# radio.net
KiCad netlist of a schematic drawn in Altium Designer
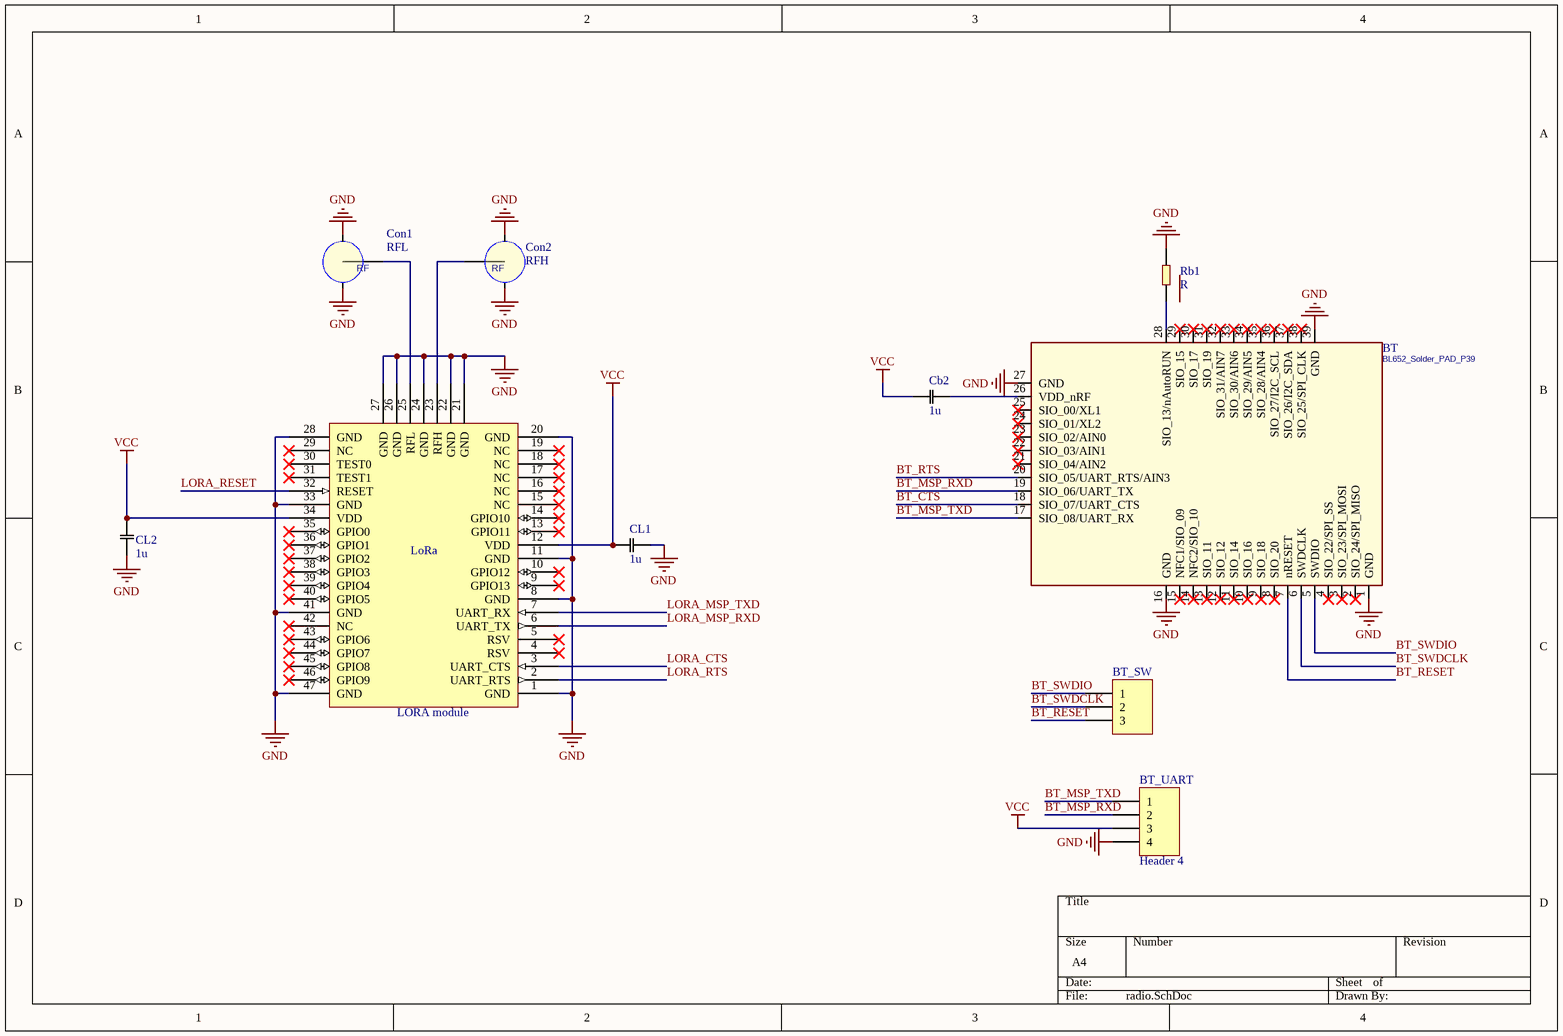
[diagram p0: radio.SchDoc]

(export (version "E")
  (design (tool "Eeschema 10.0.6"))
  (components
    (comp (ref "BT")
      (value "BL652_Solder_PAD_P39")
      (footprint "XCVR_BL652-SA-01")
      (description "BL652 Solder PAD")
      (libsource (lib "env_sens") (part "BL652_Solder_PAD_P39"))
    )
    (comp (ref "BT_SW")
      (value "~")
      (footprint "HDR1X3")
      (description "Header, 3-Pin")
      (fields (field (name "PUBLISHER") "Altium Limited"))
      (libsource (lib "Miscellaneous Connectors") (part "Header 3"))
    )
    (comp (ref "BT_UART")
      (value "Header 4")
      (footprint "HDR1X4")
      (description "Header, 4-Pin")
      (fields (field (name "PUBLISHER") "Altium Limited"))
      (libsource (lib "Miscellaneous Connectors") (part "Header 4"))
    )
    (comp (ref "Cb2")
      (value "1u")
      (footprint "603")
      (description "Capacitor")
      (libsource (lib "pass_comp") (part "C"))
    )
    (comp (ref "CL1")
      (value "1u")
      (footprint "603")
      (description "Capacitor")
      (libsource (lib "pass_comp") (part "C"))
    )
    (comp (ref "CL2")
      (value "1u")
      (footprint "603")
      (description "Capacitor")
      (libsource (lib "pass_comp") (part "C"))
    )
    (comp (ref "Con1")
      (value "RFL")
      (footprint "IPEX")
      (description "SMA PCB Edge Receptacle")
      (libsource (lib "env_sens") (part "IPEX/U.FL"))
    )
    (comp (ref "Con2")
      (value "RFH")
      (footprint "IPEX")
      (description "SMA PCB Edge Receptacle")
      (libsource (lib "env_sens") (part "IPEX/U.FL"))
    )
    (comp (ref "LoRa") (value "LORA module") (footprint "RN2483") (libsource (lib "env_sens") (part "Lora")))
    (comp (ref "Rb1")
      (value "R")
      (footprint "603")
      (description "Resistor")
      (libsource (lib "pass_comp") (part "R"))
    )
  )
  (nets
    (net (code "1") (name "/BT_CTS") (class "Default")
      (node (ref "BT") (pin "18") (pinfunction "SIO_07/UART_CTS_18") (pintype "passive"))
    )
    (net (code "2") (name "/BT_MSP_RXD") (class "Default")
      (node (ref "BT") (pin "19") (pinfunction "SIO_06/UART_TX_19") (pintype "passive"))
      (node (ref "BT_UART") (pin "2") (pinfunction "2_2") (pintype "passive"))
    )
    (net (code "3") (name "/BT_MSP_TXD") (class "Default")
      (node (ref "BT") (pin "17") (pinfunction "SIO_08/UART_RX_17") (pintype "passive"))
      (node (ref "BT_UART") (pin "1") (pinfunction "1_1") (pintype "passive"))
    )
    (net (code "4") (name "/BT_RESET") (class "Default")
      (node (ref "BT") (pin "7") (pinfunction "nRESET_7") (pintype "passive"))
      (node (ref "BT_SW") (pin "3") (pinfunction "3_3") (pintype "passive"))
    )
    (net (code "5") (name "/BT_RTS") (class "Default")
      (node (ref "BT") (pin "20") (pinfunction "SIO_05/UART_RTS/AIN3_20") (pintype "passive"))
    )
    (net (code "6") (name "/BT_SWDCLK") (class "Default")
      (node (ref "BT") (pin "6") (pinfunction "SWDCLK_6") (pintype "passive"))
      (node (ref "BT_SW") (pin "2") (pinfunction "2_2") (pintype "passive"))
    )
    (net (code "7") (name "/BT_SWDIO") (class "Default")
      (node (ref "BT") (pin "5") (pinfunction "SWDIO_5") (pintype "passive"))
      (node (ref "BT_SW") (pin "1") (pinfunction "1_1") (pintype "passive"))
    )
    (net (code "8") (name "/LORA_CTS") (class "Default")
      (node (ref "LoRa") (pin "3") (pinfunction "UART_CTS_3") (pintype "input"))
    )
    (net (code "9") (name "/LORA_MSP_RXD") (class "Default")
      (node (ref "LoRa") (pin "6") (pinfunction "UART_TX_6") (pintype "output"))
    )
    (net (code "10") (name "/LORA_MSP_TXD") (class "Default")
      (node (ref "LoRa") (pin "7") (pinfunction "UART_RX_7") (pintype "input"))
    )
    (net (code "11") (name "/LORA_RESET") (class "Default")
      (node (ref "LoRa") (pin "32") (pinfunction "RESET_32") (pintype "input"))
    )
    (net (code "12") (name "/LORA_RTS") (class "Default")
      (node (ref "LoRa") (pin "2") (pinfunction "UART_RTS_2") (pintype "output"))
    )
    (net (code "13") (name "GND") (class "Default")
      (node (ref "BT") (pin "1") (pinfunction "GND_1") (pintype "passive"))
      (node (ref "BT") (pin "16") (pinfunction "GND_16") (pintype "passive"))
      (node (ref "BT") (pin "27") (pinfunction "GND_27") (pintype "passive"))
      (node (ref "BT") (pin "39") (pinfunction "GND_39") (pintype "passive"))
      (node (ref "BT_UART") (pin "4") (pinfunction "4_4") (pintype "passive"))
      (node (ref "CL1") (pin "2") (pintype "passive"))
      (node (ref "CL2") (pin "1") (pintype "passive"))
      (node (ref "Con1") (pin "2") (pintype "passive"))
      (node (ref "Con1") (pin "3") (pintype "passive"))
      (node (ref "Con2") (pin "2") (pintype "passive"))
      (node (ref "Con2") (pin "3") (pintype "passive"))
      (node (ref "LoRa") (pin "1") (pinfunction "GND_1") (pintype "power_in"))
      (node (ref "LoRa") (pin "11") (pinfunction "GND_11") (pintype "power_in"))
      (node (ref "LoRa") (pin "20") (pinfunction "GND_20") (pintype "power_in"))
      (node (ref "LoRa") (pin "21") (pinfunction "GND_21") (pintype "power_in"))
      (node (ref "LoRa") (pin "22") (pinfunction "GND_22") (pintype "power_in"))
      (node (ref "LoRa") (pin "24") (pinfunction "GND_24") (pintype "power_in"))
      (node (ref "LoRa") (pin "26") (pinfunction "GND_26") (pintype "power_in"))
      (node (ref "LoRa") (pin "27") (pinfunction "GND_27") (pintype "power_in"))
      (node (ref "LoRa") (pin "28") (pinfunction "GND_28") (pintype "power_in"))
      (node (ref "LoRa") (pin "33") (pinfunction "GND_33") (pintype "power_in"))
      (node (ref "LoRa") (pin "41") (pinfunction "GND_41") (pintype "power_in"))
      (node (ref "LoRa") (pin "47") (pinfunction "GND_47") (pintype "power_in"))
      (node (ref "LoRa") (pin "8") (pinfunction "GND_8") (pintype "power_in"))
      (node (ref "Rb1") (pin "1") (pintype "passive"))
    )
    (net (code "14") (name "Net-(BT-SIO_13{slash}nAutoRUN)") (class "Default")
      (node (ref "BT") (pin "28") (pinfunction "SIO_13/nAutoRUN_28") (pintype "passive"))
      (node (ref "Rb1") (pin "2") (pintype "passive"))
    )
    (net (code "15") (name "Net-(BT-VDD_nRF)") (class "Default")
      (node (ref "BT") (pin "26") (pinfunction "VDD_nRF_26") (pintype "passive"))
      (node (ref "Cb2") (pin "2") (pintype "passive"))
    )
    (net (code "16") (name "Net-(Con1-RF)") (class "Default")
      (node (ref "Con1") (pin "1") (pinfunction "RF_1") (pintype "passive"))
      (node (ref "LoRa") (pin "25") (pinfunction "RFL_25") (pintype "passive"))
    )
    (net (code "17") (name "Net-(Con2-RF)") (class "Default")
      (node (ref "Con2") (pin "1") (pinfunction "RF_1") (pintype "passive"))
      (node (ref "LoRa") (pin "23") (pinfunction "RFH_23") (pintype "passive"))
    )
    (net (code "18") (name "VCC") (class "Default")
      (node (ref "BT_UART") (pin "3") (pinfunction "3_3") (pintype "passive"))
      (node (ref "CL1") (pin "1") (pintype "passive"))
      (node (ref "CL2") (pin "2") (pintype "passive"))
      (node (ref "Cb2") (pin "1") (pintype "passive"))
      (node (ref "LoRa") (pin "12") (pinfunction "VDD_12") (pintype "passive"))
      (node (ref "LoRa") (pin "34") (pinfunction "VDD_34") (pintype "power_in"))
    )
    (net (code "19") (name "unconnected-(BT-NFC1{slash}SIO_09-Pad15)") (class "Default")
      (node (ref "BT") (pin "15") (pinfunction "NFC1/SIO_09_15") (pintype "passive+no_connect"))
    )
    (net (code "20") (name "unconnected-(BT-NFC2{slash}SIO_10-Pad14)") (class "Default")
      (node (ref "BT") (pin "14") (pinfunction "NFC2/SIO_10_14") (pintype "passive+no_connect"))
    )
    (net (code "21") (name "unconnected-(BT-SIO_00{slash}XL1-Pad25)") (class "Default")
      (node (ref "BT") (pin "25") (pinfunction "SIO_00/XL1_25") (pintype "passive+no_connect"))
    )
    (net (code "22") (name "unconnected-(BT-SIO_01{slash}XL2-Pad24)") (class "Default")
      (node (ref "BT") (pin "24") (pinfunction "SIO_01/XL2_24") (pintype "passive+no_connect"))
    )
    (net (code "23") (name "unconnected-(BT-SIO_02{slash}AIN0-Pad23)") (class "Default")
      (node (ref "BT") (pin "23") (pinfunction "SIO_02/AIN0_23") (pintype "passive+no_connect"))
    )
    (net (code "24") (name "unconnected-(BT-SIO_03{slash}AIN1-Pad22)") (class "Default")
      (node (ref "BT") (pin "22") (pinfunction "SIO_03/AIN1_22") (pintype "passive+no_connect"))
    )
    (net (code "25") (name "unconnected-(BT-SIO_04{slash}AIN2-Pad21)") (class "Default")
      (node (ref "BT") (pin "21") (pinfunction "SIO_04/AIN2_21") (pintype "passive+no_connect"))
    )
    (net (code "26") (name "unconnected-(BT-SIO_11-Pad13)") (class "Default")
      (node (ref "BT") (pin "13") (pinfunction "SIO_11_13") (pintype "passive+no_connect"))
    )
    (net (code "27") (name "unconnected-(BT-SIO_12-Pad12)") (class "Default")
      (node (ref "BT") (pin "12") (pinfunction "SIO_12_12") (pintype "passive+no_connect"))
    )
    (net (code "28") (name "unconnected-(BT-SIO_14-Pad11)") (class "Default")
      (node (ref "BT") (pin "11") (pinfunction "SIO_14_11") (pintype "passive+no_connect"))
    )
    (net (code "29") (name "unconnected-(BT-SIO_15-Pad29)") (class "Default")
      (node (ref "BT") (pin "29") (pinfunction "SIO_15_29") (pintype "passive+no_connect"))
    )
    (net (code "30") (name "unconnected-(BT-SIO_16-Pad10)") (class "Default")
      (node (ref "BT") (pin "10") (pinfunction "SIO_16_10") (pintype "passive+no_connect"))
    )
    (net (code "31") (name "unconnected-(BT-SIO_17-Pad30)") (class "Default")
      (node (ref "BT") (pin "30") (pinfunction "SIO_17_30") (pintype "passive+no_connect"))
    )
    (net (code "32") (name "unconnected-(BT-SIO_18-Pad9)") (class "Default")
      (node (ref "BT") (pin "9") (pinfunction "SIO_18_9") (pintype "passive+no_connect"))
    )
    (net (code "33") (name "unconnected-(BT-SIO_19-Pad31)") (class "Default")
      (node (ref "BT") (pin "31") (pinfunction "SIO_19_31") (pintype "passive+no_connect"))
    )
    (net (code "34") (name "unconnected-(BT-SIO_20-Pad8)") (class "Default")
      (node (ref "BT") (pin "8") (pinfunction "SIO_20_8") (pintype "passive+no_connect"))
    )
    (net (code "35") (name "unconnected-(BT-SIO_22{slash}SPI_SS-Pad4)") (class "Default")
      (node (ref "BT") (pin "4") (pinfunction "SIO_22/SPI_SS_4") (pintype "passive+no_connect"))
    )
    (net (code "36") (name "unconnected-(BT-SIO_23{slash}SPI_MOSI-Pad3)") (class "Default")
      (node (ref "BT") (pin "3") (pinfunction "SIO_23/SPI_MOSI_3") (pintype "passive+no_connect"))
    )
    (net (code "37") (name "unconnected-(BT-SIO_24{slash}SPI_MISO-Pad2)") (class "Default")
      (node (ref "BT") (pin "2") (pinfunction "SIO_24/SPI_MISO_2") (pintype "passive+no_connect"))
    )
    (net (code "38") (name "unconnected-(BT-SIO_25{slash}SPI_CLK-Pad38)") (class "Default")
      (node (ref "BT") (pin "38") (pinfunction "SIO_25/SPI_CLK_38") (pintype "passive+no_connect"))
    )
    (net (code "39") (name "unconnected-(BT-SIO_26{slash}I2C_SDA-Pad37)") (class "Default")
      (node (ref "BT") (pin "37") (pinfunction "SIO_26/I2C_SDA_37") (pintype "passive+no_connect"))
    )
    (net (code "40") (name "unconnected-(BT-SIO_27{slash}I2C_SCL-Pad36)") (class "Default")
      (node (ref "BT") (pin "36") (pinfunction "SIO_27/I2C_SCL_36") (pintype "passive+no_connect"))
    )
    (net (code "41") (name "unconnected-(BT-SIO_28{slash}AIN4-Pad35)") (class "Default")
      (node (ref "BT") (pin "35") (pinfunction "SIO_28/AIN4_35") (pintype "passive+no_connect"))
    )
    (net (code "42") (name "unconnected-(BT-SIO_29{slash}AIN5-Pad34)") (class "Default")
      (node (ref "BT") (pin "34") (pinfunction "SIO_29/AIN5_34") (pintype "passive+no_connect"))
    )
    (net (code "43") (name "unconnected-(BT-SIO_30{slash}AIN6-Pad33)") (class "Default")
      (node (ref "BT") (pin "33") (pinfunction "SIO_30/AIN6_33") (pintype "passive+no_connect"))
    )
    (net (code "44") (name "unconnected-(BT-SIO_31{slash}AIN7-Pad32)") (class "Default")
      (node (ref "BT") (pin "32") (pinfunction "SIO_31/AIN7_32") (pintype "passive+no_connect"))
    )
    (net (code "45") (name "unconnected-(LoRa-GPIO0-Pad35)") (class "Default")
      (node (ref "LoRa") (pin "35") (pinfunction "GPIO0_35") (pintype "bidirectional+no_connect"))
    )
    (net (code "46") (name "unconnected-(LoRa-GPIO1-Pad36)") (class "Default")
      (node (ref "LoRa") (pin "36") (pinfunction "GPIO1_36") (pintype "bidirectional+no_connect"))
    )
    (net (code "47") (name "unconnected-(LoRa-GPIO2-Pad37)") (class "Default")
      (node (ref "LoRa") (pin "37") (pinfunction "GPIO2_37") (pintype "bidirectional+no_connect"))
    )
    (net (code "48") (name "unconnected-(LoRa-GPIO3-Pad38)") (class "Default")
      (node (ref "LoRa") (pin "38") (pinfunction "GPIO3_38") (pintype "bidirectional+no_connect"))
    )
    (net (code "49") (name "unconnected-(LoRa-GPIO4-Pad39)") (class "Default")
      (node (ref "LoRa") (pin "39") (pinfunction "GPIO4_39") (pintype "bidirectional+no_connect"))
    )
    (net (code "50") (name "unconnected-(LoRa-GPIO5-Pad40)") (class "Default")
      (node (ref "LoRa") (pin "40") (pinfunction "GPIO5_40") (pintype "bidirectional+no_connect"))
    )
    (net (code "51") (name "unconnected-(LoRa-GPIO6-Pad43)") (class "Default")
      (node (ref "LoRa") (pin "43") (pinfunction "GPIO6_43") (pintype "bidirectional+no_connect"))
    )
    (net (code "52") (name "unconnected-(LoRa-GPIO7-Pad44)") (class "Default")
      (node (ref "LoRa") (pin "44") (pinfunction "GPIO7_44") (pintype "bidirectional+no_connect"))
    )
    (net (code "53") (name "unconnected-(LoRa-GPIO8-Pad45)") (class "Default")
      (node (ref "LoRa") (pin "45") (pinfunction "GPIO8_45") (pintype "bidirectional+no_connect"))
    )
    (net (code "54") (name "unconnected-(LoRa-GPIO9-Pad46)") (class "Default")
      (node (ref "LoRa") (pin "46") (pinfunction "GPIO9_46") (pintype "bidirectional+no_connect"))
    )
    (net (code "55") (name "unconnected-(LoRa-GPIO10-Pad14)") (class "Default")
      (node (ref "LoRa") (pin "14") (pinfunction "GPIO10_14") (pintype "bidirectional+no_connect"))
    )
    (net (code "56") (name "unconnected-(LoRa-GPIO11-Pad13)") (class "Default")
      (node (ref "LoRa") (pin "13") (pinfunction "GPIO11_13") (pintype "bidirectional+no_connect"))
    )
    (net (code "57") (name "unconnected-(LoRa-GPIO12-Pad10)") (class "Default")
      (node (ref "LoRa") (pin "10") (pinfunction "GPIO12_10") (pintype "bidirectional+no_connect"))
    )
    (net (code "58") (name "unconnected-(LoRa-GPIO13-Pad9)") (class "Default")
      (node (ref "LoRa") (pin "9") (pinfunction "GPIO13_9") (pintype "bidirectional+no_connect"))
    )
    (net (code "59") (name "unconnected-(LoRa-NC-Pad15)") (class "Default")
      (node (ref "LoRa") (pin "15") (pinfunction "NC_15") (pintype "passive+no_connect"))
    )
    (net (code "60") (name "unconnected-(LoRa-NC-Pad16)") (class "Default")
      (node (ref "LoRa") (pin "16") (pinfunction "NC_16") (pintype "passive+no_connect"))
    )
    (net (code "61") (name "unconnected-(LoRa-NC-Pad17)") (class "Default")
      (node (ref "LoRa") (pin "17") (pinfunction "NC_17") (pintype "passive+no_connect"))
    )
    (net (code "62") (name "unconnected-(LoRa-NC-Pad18)") (class "Default")
      (node (ref "LoRa") (pin "18") (pinfunction "NC_18") (pintype "passive+no_connect"))
    )
    (net (code "63") (name "unconnected-(LoRa-NC-Pad19)") (class "Default")
      (node (ref "LoRa") (pin "19") (pinfunction "NC_19") (pintype "passive+no_connect"))
    )
    (net (code "64") (name "unconnected-(LoRa-NC-Pad29)") (class "Default")
      (node (ref "LoRa") (pin "29") (pinfunction "NC_29") (pintype "passive+no_connect"))
    )
    (net (code "65") (name "unconnected-(LoRa-NC-Pad42)") (class "Default")
      (node (ref "LoRa") (pin "42") (pinfunction "NC_42") (pintype "passive+no_connect"))
    )
    (net (code "66") (name "unconnected-(LoRa-RSV-Pad4)") (class "Default")
      (node (ref "LoRa") (pin "4") (pinfunction "RSV_4") (pintype "passive+no_connect"))
    )
    (net (code "67") (name "unconnected-(LoRa-RSV-Pad5)") (class "Default")
      (node (ref "LoRa") (pin "5") (pinfunction "RSV_5") (pintype "passive+no_connect"))
    )
    (net (code "68") (name "unconnected-(LoRa-TEST0-Pad30)") (class "Default")
      (node (ref "LoRa") (pin "30") (pinfunction "TEST0_30") (pintype "passive+no_connect"))
    )
    (net (code "69") (name "unconnected-(LoRa-TEST1-Pad31)") (class "Default")
      (node (ref "LoRa") (pin "31") (pinfunction "TEST1_31") (pintype "passive+no_connect"))
    )
  )
)
